# Power_Unit.net
KiCad netlist of a schematic drawn in Altium Designer
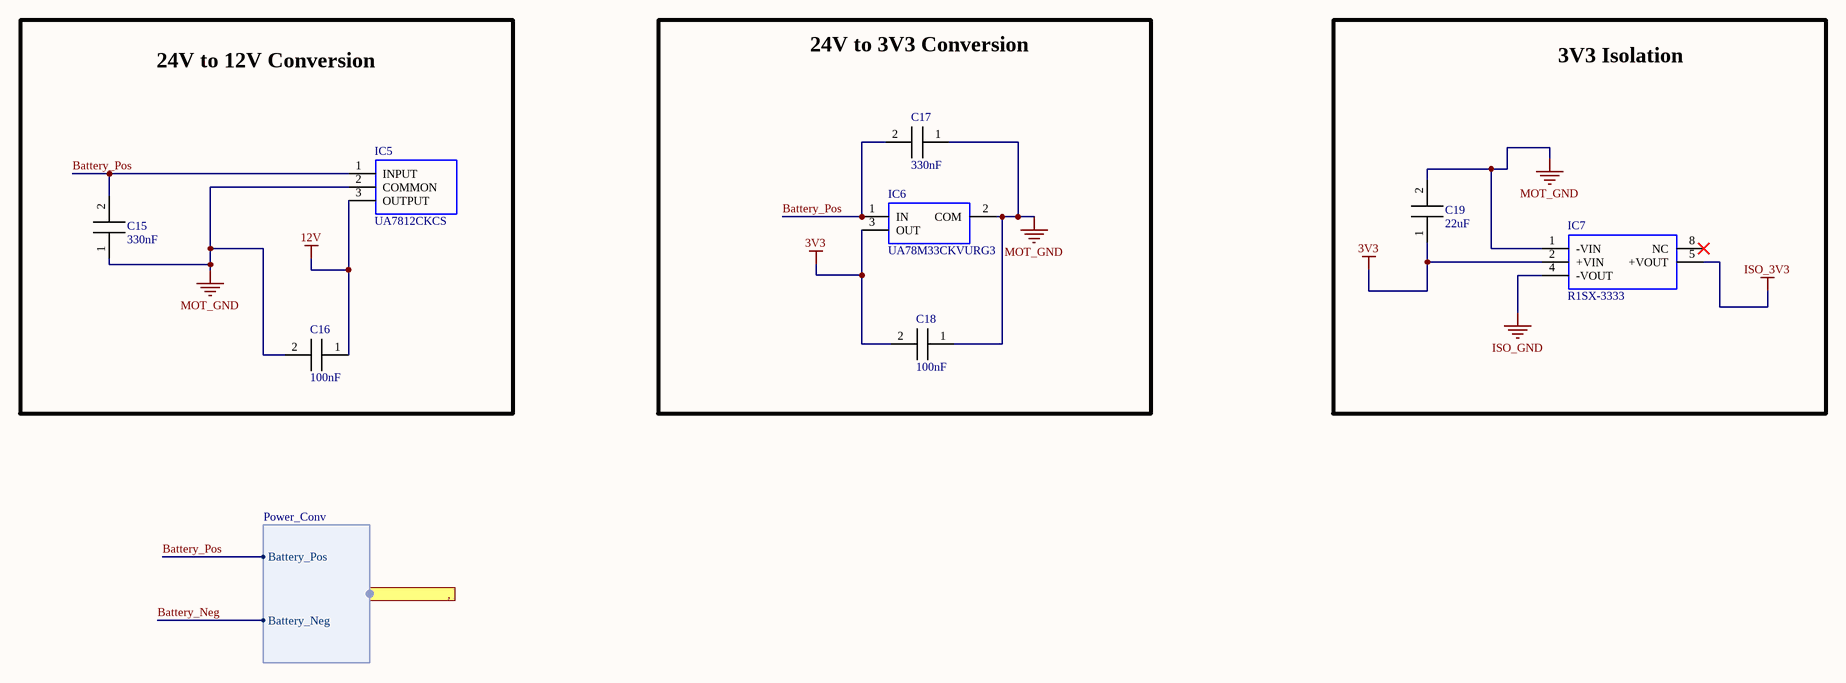
[diagram p0: Power_Unit.SchDoc]

(export (version "E")
  (design (tool "Eeschema 10.0.6"))
  (components
    (comp (ref "C15")
      (value "CAP 330nF")
      (fields (field (name "PARAMETER 1") "330nF"))
      (libsource (lib "Schlib1") (part "CAP 330nF"))
    )
    (comp (ref "C16")
      (value "CAP 100nF")
      (fields (field (name "PARAMETER 1") "100nF"))
      (libsource (lib "Schlib1") (part "CAP 100nF"))
    )
    (comp (ref "C17")
      (value "CAP 330nF")
      (fields (field (name "PARAMETER 1") "330nF"))
      (libsource (lib "Schlib1") (part "CAP 330nF"))
    )
    (comp (ref "C18")
      (value "CAP 100nF")
      (fields (field (name "PARAMETER 1") "100nF"))
      (libsource (lib "Schlib1") (part "CAP 100nF"))
    )
    (comp (ref "C19")
      (value "CAP  22uF")
      (fields (field (name "PARAMETER 1") "22uF"))
      (libsource (lib "Schlib1") (part "CAP  22uF"))
    )
    (comp (ref "IC5")
      (value "UA7812CKCS")
      (footprint "UA7812CKCS")
      (libsource (lib "Schlib1") (part "IC, LVR, UA7812CKCS"))
    )
    (comp (ref "IC6")
      (value "UA78M33CKVURG3")
      (footprint "UA78M33CKVURG3")
      (libsource (lib "Schlib1") (part "IC, LVR, UA78M33CKVURG3, 24/3V3"))
    )
    (comp (ref "IC7")
      (value "R1SX-3333")
      (footprint "R1SX_3333")
      (libsource (lib "Schlib1") (part "IC, DC/DC, ISO, R1SX-3333"))
    )
  )
  (nets
    (net (code "3") (name "/Battery_Pos") (class "Default")
      (node (ref "C15") (pin "2") (pinfunction "2_2") (pintype "passive"))
      (node (ref "C17") (pin "2") (pinfunction "2_2") (pintype "passive"))
      (node (ref "IC5") (pin "1") (pinfunction "INPUT_1") (pintype "passive"))
      (node (ref "IC6") (pin "1") (pinfunction "IN_1") (pintype "passive"))
    )
    (net (code "5") (name "3V3") (class "Default")
      (node (ref "C18") (pin "2") (pinfunction "2_2") (pintype "passive"))
      (node (ref "C19") (pin "1") (pinfunction "1_1") (pintype "passive"))
      (node (ref "IC6") (pin "3") (pinfunction "OUT_3") (pintype "passive"))
      (node (ref "IC7") (pin "2") (pinfunction "+VIN_2") (pintype "passive"))
    )
    (net (code "6") (name "12V") (class "Default")
      (node (ref "C16") (pin "1") (pinfunction "1_1") (pintype "passive"))
      (node (ref "IC5") (pin "3") (pinfunction "OUTPUT_3") (pintype "passive"))
    )
    (net (code "7") (name "ISO_3V3") (class "Default")
      (node (ref "IC7") (pin "5") (pinfunction "+VOUT_5") (pintype "passive"))
    )
    (net (code "8") (name "ISO_GND") (class "Default")
      (node (ref "IC7") (pin "4") (pinfunction "-VOUT_4") (pintype "passive"))
    )
    (net (code "9") (name "MOT_GND") (class "Default")
      (node (ref "C15") (pin "1") (pinfunction "1_1") (pintype "passive"))
      (node (ref "C16") (pin "2") (pinfunction "2_2") (pintype "passive"))
      (node (ref "C17") (pin "1") (pinfunction "1_1") (pintype "passive"))
      (node (ref "C18") (pin "1") (pinfunction "1_1") (pintype "passive"))
      (node (ref "C19") (pin "2") (pinfunction "2_2") (pintype "passive"))
      (node (ref "IC5") (pin "2") (pinfunction "COMMON_2") (pintype "passive"))
      (node (ref "IC6") (pin "2") (pinfunction "COM_2") (pintype "passive"))
      (node (ref "IC7") (pin "1") (pinfunction "-VIN_1") (pintype "passive"))
    )
    (net (code "10") (name "unconnected-(IC7-NC-Pad8)") (class "Default")
      (node (ref "IC7") (pin "8") (pinfunction "NC_8") (pintype "passive+no_connect"))
    )
  )
)
